# bai_2.net
KiCad netlist of a schematic drawn in Altium Designer
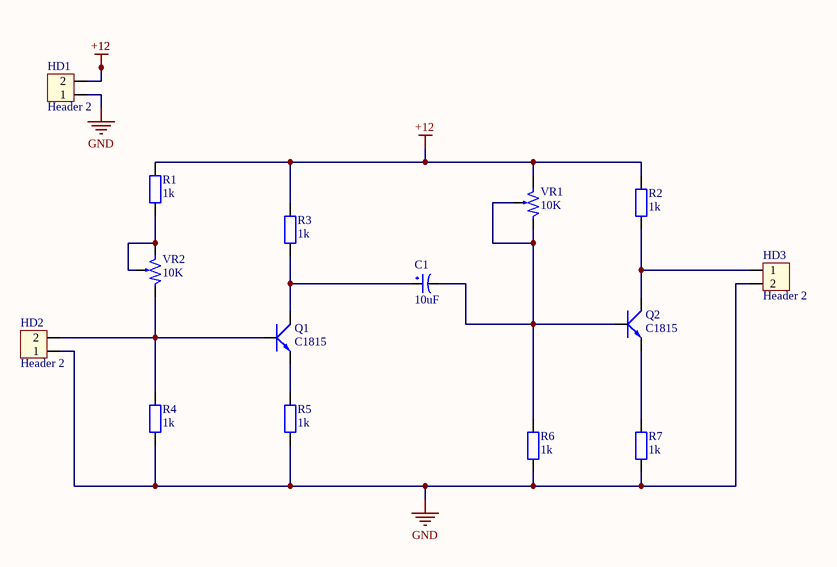
[diagram p0: bai 2.SchDoc]

(export (version "E")
  (design (tool "Eeschema 10.0.6"))
  (components
    (comp (ref "C1")
      (value "10uF")
      (footprint "CP1/2")
      (description "Cap P  0,1uF < 22uF , 16 - 50V")
      (libsource (lib "syhaunguyen") (part "CP1"))
    )
    (comp (ref "HD1")
      (value "Header 2")
      (footprint "HED2")
      (description "Header 2 (Green)")
      (libsource (lib "syhaunguyen") (part "Hed2"))
    )
    (comp (ref "HD2")
      (value "Header 2")
      (footprint "HED2")
      (description "Header 2 (Green)")
      (libsource (lib "syhaunguyen") (part "Hed2"))
    )
    (comp (ref "HD3")
      (value "Header 2")
      (footprint "HED2")
      (description "Header 2 (Green)")
      (libsource (lib "") (part "Hed2_1"))
    )
    (comp (ref "Q1")
      (value "C1815")
      (footprint "QTO-92")
      (description "NPN 600mW, ECB")
      (libsource (lib "syhaunguyen") (part "C1815"))
    )
    (comp (ref "Q2")
      (value "C1815")
      (footprint "QTO-92")
      (description "NPN 600mW, ECB")
      (libsource (lib "syhaunguyen") (part "C1815"))
    )
    (comp (ref "R1")
      (value "1k")
      (footprint "R1/4W")
      (description "Resistor 1/4W")
      (libsource (lib "syhaunguyen") (part "R1/4W"))
    )
    (comp (ref "R2")
      (value "1k")
      (footprint "R1/4W")
      (description "Resistor 1/4W")
      (libsource (lib "syhaunguyen") (part "R1/4W"))
    )
    (comp (ref "R3")
      (value "1k")
      (footprint "R1/4W")
      (description "Resistor 1/4W")
      (libsource (lib "syhaunguyen") (part "R1/4W"))
    )
    (comp (ref "R4")
      (value "1k")
      (footprint "R1/4W")
      (description "Resistor 1/4W")
      (libsource (lib "syhaunguyen") (part "R1/4W"))
    )
    (comp (ref "R5")
      (value "1k")
      (footprint "R1/4W")
      (description "Resistor 1/4W")
      (libsource (lib "syhaunguyen") (part "R1/4W"))
    )
    (comp (ref "R6")
      (value "1k")
      (footprint "R1/4W")
      (description "Resistor 1/4W")
      (libsource (lib "syhaunguyen") (part "R1/4W"))
    )
    (comp (ref "R7")
      (value "1k")
      (footprint "R1/4W")
      (description "Resistor 1/4W")
      (libsource (lib "syhaunguyen") (part "R1/4W"))
    )
    (comp (ref "VR1")
      (value "10K")
      (footprint "VR")
      (description "Var Resistor")
      (libsource (lib "syhaunguyen") (part "VR1"))
    )
    (comp (ref "VR2")
      (value "10K")
      (footprint "VR")
      (description "Var Resistor")
      (libsource (lib "syhaunguyen") (part "VR1"))
    )
  )
  (nets
    (net (code "1") (name "+12") (class "Default")
      (node (ref "HD1") (pin "2") (pinfunction "2_2") (pintype "passive"))
      (node (ref "R1") (pin "2") (pinfunction "2_2") (pintype "passive"))
      (node (ref "R2") (pin "2") (pinfunction "2_2") (pintype "passive"))
      (node (ref "R3") (pin "2") (pinfunction "2_2") (pintype "passive"))
      (node (ref "VR1") (pin "3") (pinfunction "3_3") (pintype "passive"))
    )
    (net (code "2") (name "GND") (class "Default")
      (node (ref "HD1") (pin "1") (pinfunction "1_1") (pintype "passive"))
      (node (ref "HD2") (pin "1") (pinfunction "1_1") (pintype "passive"))
      (node (ref "HD3") (pin "2") (pinfunction "2_2") (pintype "passive"))
      (node (ref "R4") (pin "1") (pinfunction "1_1") (pintype "passive"))
      (node (ref "R5") (pin "2") (pinfunction "2_2") (pintype "passive"))
      (node (ref "R6") (pin "1") (pinfunction "1_1") (pintype "passive"))
      (node (ref "R7") (pin "1") (pinfunction "1_1") (pintype "passive"))
    )
    (net (code "3") (name "Net-(Q1-B)") (class "Default")
      (node (ref "HD2") (pin "2") (pinfunction "2_2") (pintype "passive"))
      (node (ref "Q1") (pin "3") (pinfunction "B_3") (pintype "passive"))
      (node (ref "R4") (pin "2") (pinfunction "2_2") (pintype "passive"))
      (node (ref "VR2") (pin "1") (pinfunction "1_1") (pintype "passive"))
    )
    (net (code "4") (name "Net-(Q1-C)") (class "Default")
      (node (ref "C1") (pin "1") (pinfunction "1_1") (pintype "passive"))
      (node (ref "Q1") (pin "2") (pinfunction "C_2") (pintype "passive"))
      (node (ref "R3") (pin "1") (pinfunction "1_1") (pintype "passive"))
    )
    (net (code "5") (name "Net-(Q1-E)") (class "Default")
      (node (ref "Q1") (pin "1") (pinfunction "E_1") (pintype "passive"))
      (node (ref "R5") (pin "1") (pinfunction "1_1") (pintype "passive"))
    )
    (net (code "6") (name "Net-(Q2-B)") (class "Default")
      (node (ref "C1") (pin "2") (pinfunction "2_2") (pintype "passive"))
      (node (ref "Q2") (pin "3") (pinfunction "B_3") (pintype "passive"))
      (node (ref "R6") (pin "2") (pinfunction "2_2") (pintype "passive"))
      (node (ref "VR1") (pin "1") (pinfunction "1_1") (pintype "passive"))
      (node (ref "VR1") (pin "2") (pinfunction "2_2") (pintype "passive"))
    )
    (net (code "7") (name "Net-(Q2-C)") (class "Default")
      (node (ref "HD3") (pin "1") (pinfunction "1_1") (pintype "passive"))
      (node (ref "Q2") (pin "2") (pinfunction "C_2") (pintype "passive"))
      (node (ref "R2") (pin "1") (pinfunction "1_1") (pintype "passive"))
    )
    (net (code "8") (name "Net-(Q2-E)") (class "Default")
      (node (ref "Q2") (pin "1") (pinfunction "E_1") (pintype "passive"))
      (node (ref "R7") (pin "2") (pinfunction "2_2") (pintype "passive"))
    )
    (net (code "9") (name "Net-(R1-Pad1)") (class "Default")
      (node (ref "R1") (pin "1") (pinfunction "1_1") (pintype "passive"))
      (node (ref "VR2") (pin "2") (pinfunction "2_2") (pintype "passive"))
      (node (ref "VR2") (pin "3") (pinfunction "3_3") (pintype "passive"))
    )
  )
)
